# LightSensorsButtons.net
KiCad netlist of a schematic drawn in Altium Designer
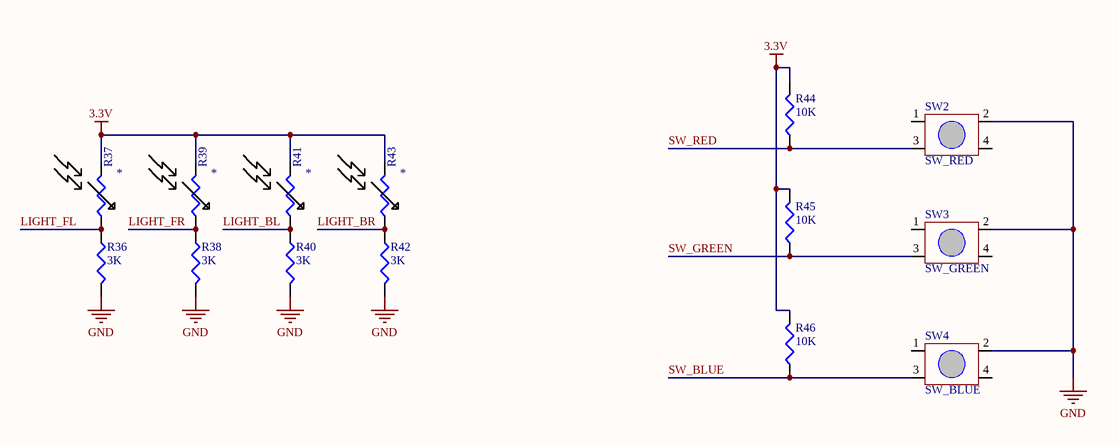
[diagram p0: LightSensorsButtons.SchDoc]

(export (version "E")
  (design (tool "Eeschema 10.0.6"))
  (components
    (comp (ref "R36")
      (value "3K")
      (footprint "RESC1608L")
      (description "Resistor")
      (fields (field (name "Comment") "Res3") (field (name "PUBLISHER") "Altium Limited"))
      (libsource (lib "Miscellaneous Devices") (part "Res3"))
    )
    (comp (ref "R37")
      (value "photoresistor")
      (footprint "photoresistor")
      (fields (field (name "ALTIUM_VALUE") "*"))
      (libsource (lib "mrone") (part "photoresistor"))
    )
    (comp (ref "R38")
      (value "3K")
      (footprint "RESC1608L")
      (description "Resistor")
      (fields (field (name "Comment") "Res3") (field (name "PUBLISHER") "Altium Limited"))
      (libsource (lib "Miscellaneous Devices") (part "Res3"))
    )
    (comp (ref "R39")
      (value "photoresistor")
      (footprint "photoresistor")
      (fields (field (name "ALTIUM_VALUE") "*"))
      (libsource (lib "mrone") (part "photoresistor"))
    )
    (comp (ref "R40")
      (value "3K")
      (footprint "RESC1608L")
      (description "Resistor")
      (fields (field (name "Comment") "Res3") (field (name "PUBLISHER") "Altium Limited"))
      (libsource (lib "Miscellaneous Devices") (part "Res3"))
    )
    (comp (ref "R41")
      (value "photoresistor")
      (footprint "photoresistor")
      (fields (field (name "ALTIUM_VALUE") "*"))
      (libsource (lib "mrone") (part "photoresistor"))
    )
    (comp (ref "R42")
      (value "3K")
      (footprint "RESC1608L")
      (description "Resistor")
      (fields (field (name "Comment") "Res3") (field (name "PUBLISHER") "Altium Limited"))
      (libsource (lib "Miscellaneous Devices") (part "Res3"))
    )
    (comp (ref "R43")
      (value "photoresistor")
      (footprint "photoresistor")
      (fields (field (name "ALTIUM_VALUE") "*"))
      (libsource (lib "mrone") (part "photoresistor"))
    )
    (comp (ref "R44")
      (value "10K")
      (footprint "RESC1608L")
      (description "Resistor")
      (fields (field (name "Comment") "Res3") (field (name "PUBLISHER") "Altium Limited"))
      (libsource (lib "Miscellaneous Devices") (part "Res3"))
    )
    (comp (ref "R45")
      (value "10K")
      (footprint "RESC1608L")
      (description "Resistor")
      (fields (field (name "Comment") "Res3") (field (name "PUBLISHER") "Altium Limited"))
      (libsource (lib "Miscellaneous Devices") (part "Res3"))
    )
    (comp (ref "R46")
      (value "10K")
      (footprint "RESC1608L")
      (description "Resistor")
      (fields (field (name "Comment") "Res3") (field (name "PUBLISHER") "Altium Limited"))
      (libsource (lib "Miscellaneous Devices") (part "Res3"))
    )
    (comp (ref "SW2")
      (value "SW_RED")
      (footprint "SwitchTall-TL330")
      (libsource (lib "mrone") (part "Switch-TL330"))
    )
    (comp (ref "SW3")
      (value "SW_GREEN")
      (footprint "SwitchTall-TL330")
      (libsource (lib "mrone") (part "Switch-TL330"))
    )
    (comp (ref "SW4")
      (value "SW_BLUE")
      (footprint "SwitchTall-TL330")
      (libsource (lib "mrone") (part "Switch-TL330"))
    )
  )
  (nets
    (net (code "1") (name "/LIGHT_BL") (class "Default")
      (node (ref "R40") (pin "1") (pinfunction "1_1") (pintype "passive"))
      (node (ref "R41") (pin "1") (pinfunction "1_1") (pintype "passive"))
    )
    (net (code "2") (name "/LIGHT_BR") (class "Default")
      (node (ref "R42") (pin "1") (pinfunction "1_1") (pintype "passive"))
      (node (ref "R43") (pin "1") (pinfunction "1_1") (pintype "passive"))
    )
    (net (code "3") (name "/LIGHT_FL") (class "Default")
      (node (ref "R36") (pin "1") (pinfunction "1_1") (pintype "passive"))
      (node (ref "R37") (pin "1") (pinfunction "1_1") (pintype "passive"))
    )
    (net (code "4") (name "/LIGHT_FR") (class "Default")
      (node (ref "R38") (pin "1") (pinfunction "1_1") (pintype "passive"))
      (node (ref "R39") (pin "1") (pinfunction "1_1") (pintype "passive"))
    )
    (net (code "5") (name "/SW_BLUE") (class "Default")
      (node (ref "R46") (pin "1") (pinfunction "1_1") (pintype "passive"))
      (node (ref "SW4") (pin "3") (pinfunction "3_3") (pintype "passive"))
    )
    (net (code "6") (name "/SW_GREEN") (class "Default")
      (node (ref "R45") (pin "1") (pinfunction "1_1") (pintype "passive"))
      (node (ref "SW3") (pin "3") (pinfunction "3_3") (pintype "passive"))
    )
    (net (code "7") (name "/SW_RED") (class "Default")
      (node (ref "R44") (pin "1") (pinfunction "1_1") (pintype "passive"))
      (node (ref "SW2") (pin "3") (pinfunction "3_3") (pintype "passive"))
    )
    (net (code "8") (name "3.3V") (class "Default")
      (node (ref "R37") (pin "2") (pinfunction "2_2") (pintype "passive"))
      (node (ref "R39") (pin "2") (pinfunction "2_2") (pintype "passive"))
      (node (ref "R41") (pin "2") (pinfunction "2_2") (pintype "passive"))
      (node (ref "R43") (pin "2") (pinfunction "2_2") (pintype "passive"))
      (node (ref "R44") (pin "2") (pinfunction "2_2") (pintype "passive"))
      (node (ref "R45") (pin "2") (pinfunction "2_2") (pintype "passive"))
      (node (ref "R46") (pin "2") (pinfunction "2_2") (pintype "passive"))
    )
    (net (code "9") (name "GND") (class "Default")
      (node (ref "R36") (pin "2") (pinfunction "2_2") (pintype "passive"))
      (node (ref "R38") (pin "2") (pinfunction "2_2") (pintype "passive"))
      (node (ref "R40") (pin "2") (pinfunction "2_2") (pintype "passive"))
      (node (ref "R42") (pin "2") (pinfunction "2_2") (pintype "passive"))
      (node (ref "SW2") (pin "2") (pinfunction "2_2") (pintype "passive"))
      (node (ref "SW3") (pin "2") (pinfunction "2_2") (pintype "passive"))
      (node (ref "SW4") (pin "2") (pinfunction "2_2") (pintype "passive"))
    )
    (net (code "10") (name "unconnected-(SW2-Pad1)") (class "Default")
      (node (ref "SW2") (pin "1") (pinfunction "1_1") (pintype "passive"))
    )
    (net (code "11") (name "unconnected-(SW2-Pad4)") (class "Default")
      (node (ref "SW2") (pin "4") (pinfunction "4_4") (pintype "passive"))
    )
    (net (code "12") (name "unconnected-(SW3-Pad1)") (class "Default")
      (node (ref "SW3") (pin "1") (pinfunction "1_1") (pintype "passive"))
    )
    (net (code "13") (name "unconnected-(SW3-Pad4)") (class "Default")
      (node (ref "SW3") (pin "4") (pinfunction "4_4") (pintype "passive"))
    )
    (net (code "14") (name "unconnected-(SW4-Pad1)") (class "Default")
      (node (ref "SW4") (pin "1") (pinfunction "1_1") (pintype "passive"))
    )
    (net (code "15") (name "unconnected-(SW4-Pad4)") (class "Default")
      (node (ref "SW4") (pin "4") (pinfunction "4_4") (pintype "passive"))
    )
  )
)
